# LDO-3V3.net
KiCad netlist of a schematic drawn in Altium Designer
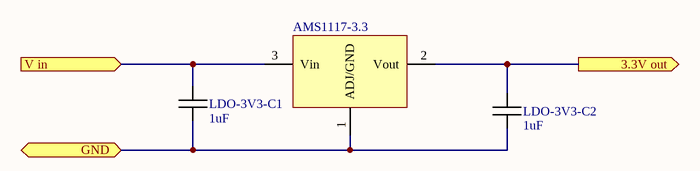
[diagram p0: LDO-3V3.SchDoc]

(export (version "E")
  (design (tool "Eeschema 10.0.6"))
  (components
    (comp (ref "AMS1117-3.3")
      (value "AMS1117")
      (footprint "SOT-223-3")
      (description "LDO 3.3V/5V/12V")
      (libsource (lib "ICs") (part "AMS1117"))
    )
    (comp (ref "LDO-3V3-C1")
      (value "1uF")
      (footprint "C 0805 / 2012")
      (libsource (lib "AMS1117 breakout") (part "Capacitor"))
    )
    (comp (ref "LDO-3V3-C2")
      (value "1uF")
      (footprint "C 0805 / 2012")
      (libsource (lib "AMS1117 breakout") (part "Capacitor"))
    )
  )
  (nets
    (net (code "1") (name "/3.3V out") (class "Default")
      (node (ref "AMS1117-3.3") (pin "2") (pinfunction "Vout_2") (pintype "passive"))
      (node (ref "LDO-3V3-C2") (pin "2") (pinfunction "2_2") (pintype "passive"))
    )
    (net (code "2") (name "/GND") (class "Default")
      (node (ref "AMS1117-3.3") (pin "1") (pinfunction "ADJ/GND_1") (pintype "passive"))
      (node (ref "LDO-3V3-C1") (pin "1") (pinfunction "1_1") (pintype "passive"))
      (node (ref "LDO-3V3-C2") (pin "1") (pinfunction "1_1") (pintype "passive"))
    )
    (net (code "3") (name "/V in") (class "Default")
      (node (ref "AMS1117-3.3") (pin "3") (pinfunction "Vin_3") (pintype "passive"))
      (node (ref "LDO-3V3-C1") (pin "2") (pinfunction "2_2") (pintype "passive"))
    )
  )
)
